# BI3.net
KiCad netlist of a schematic drawn in Altium Designer
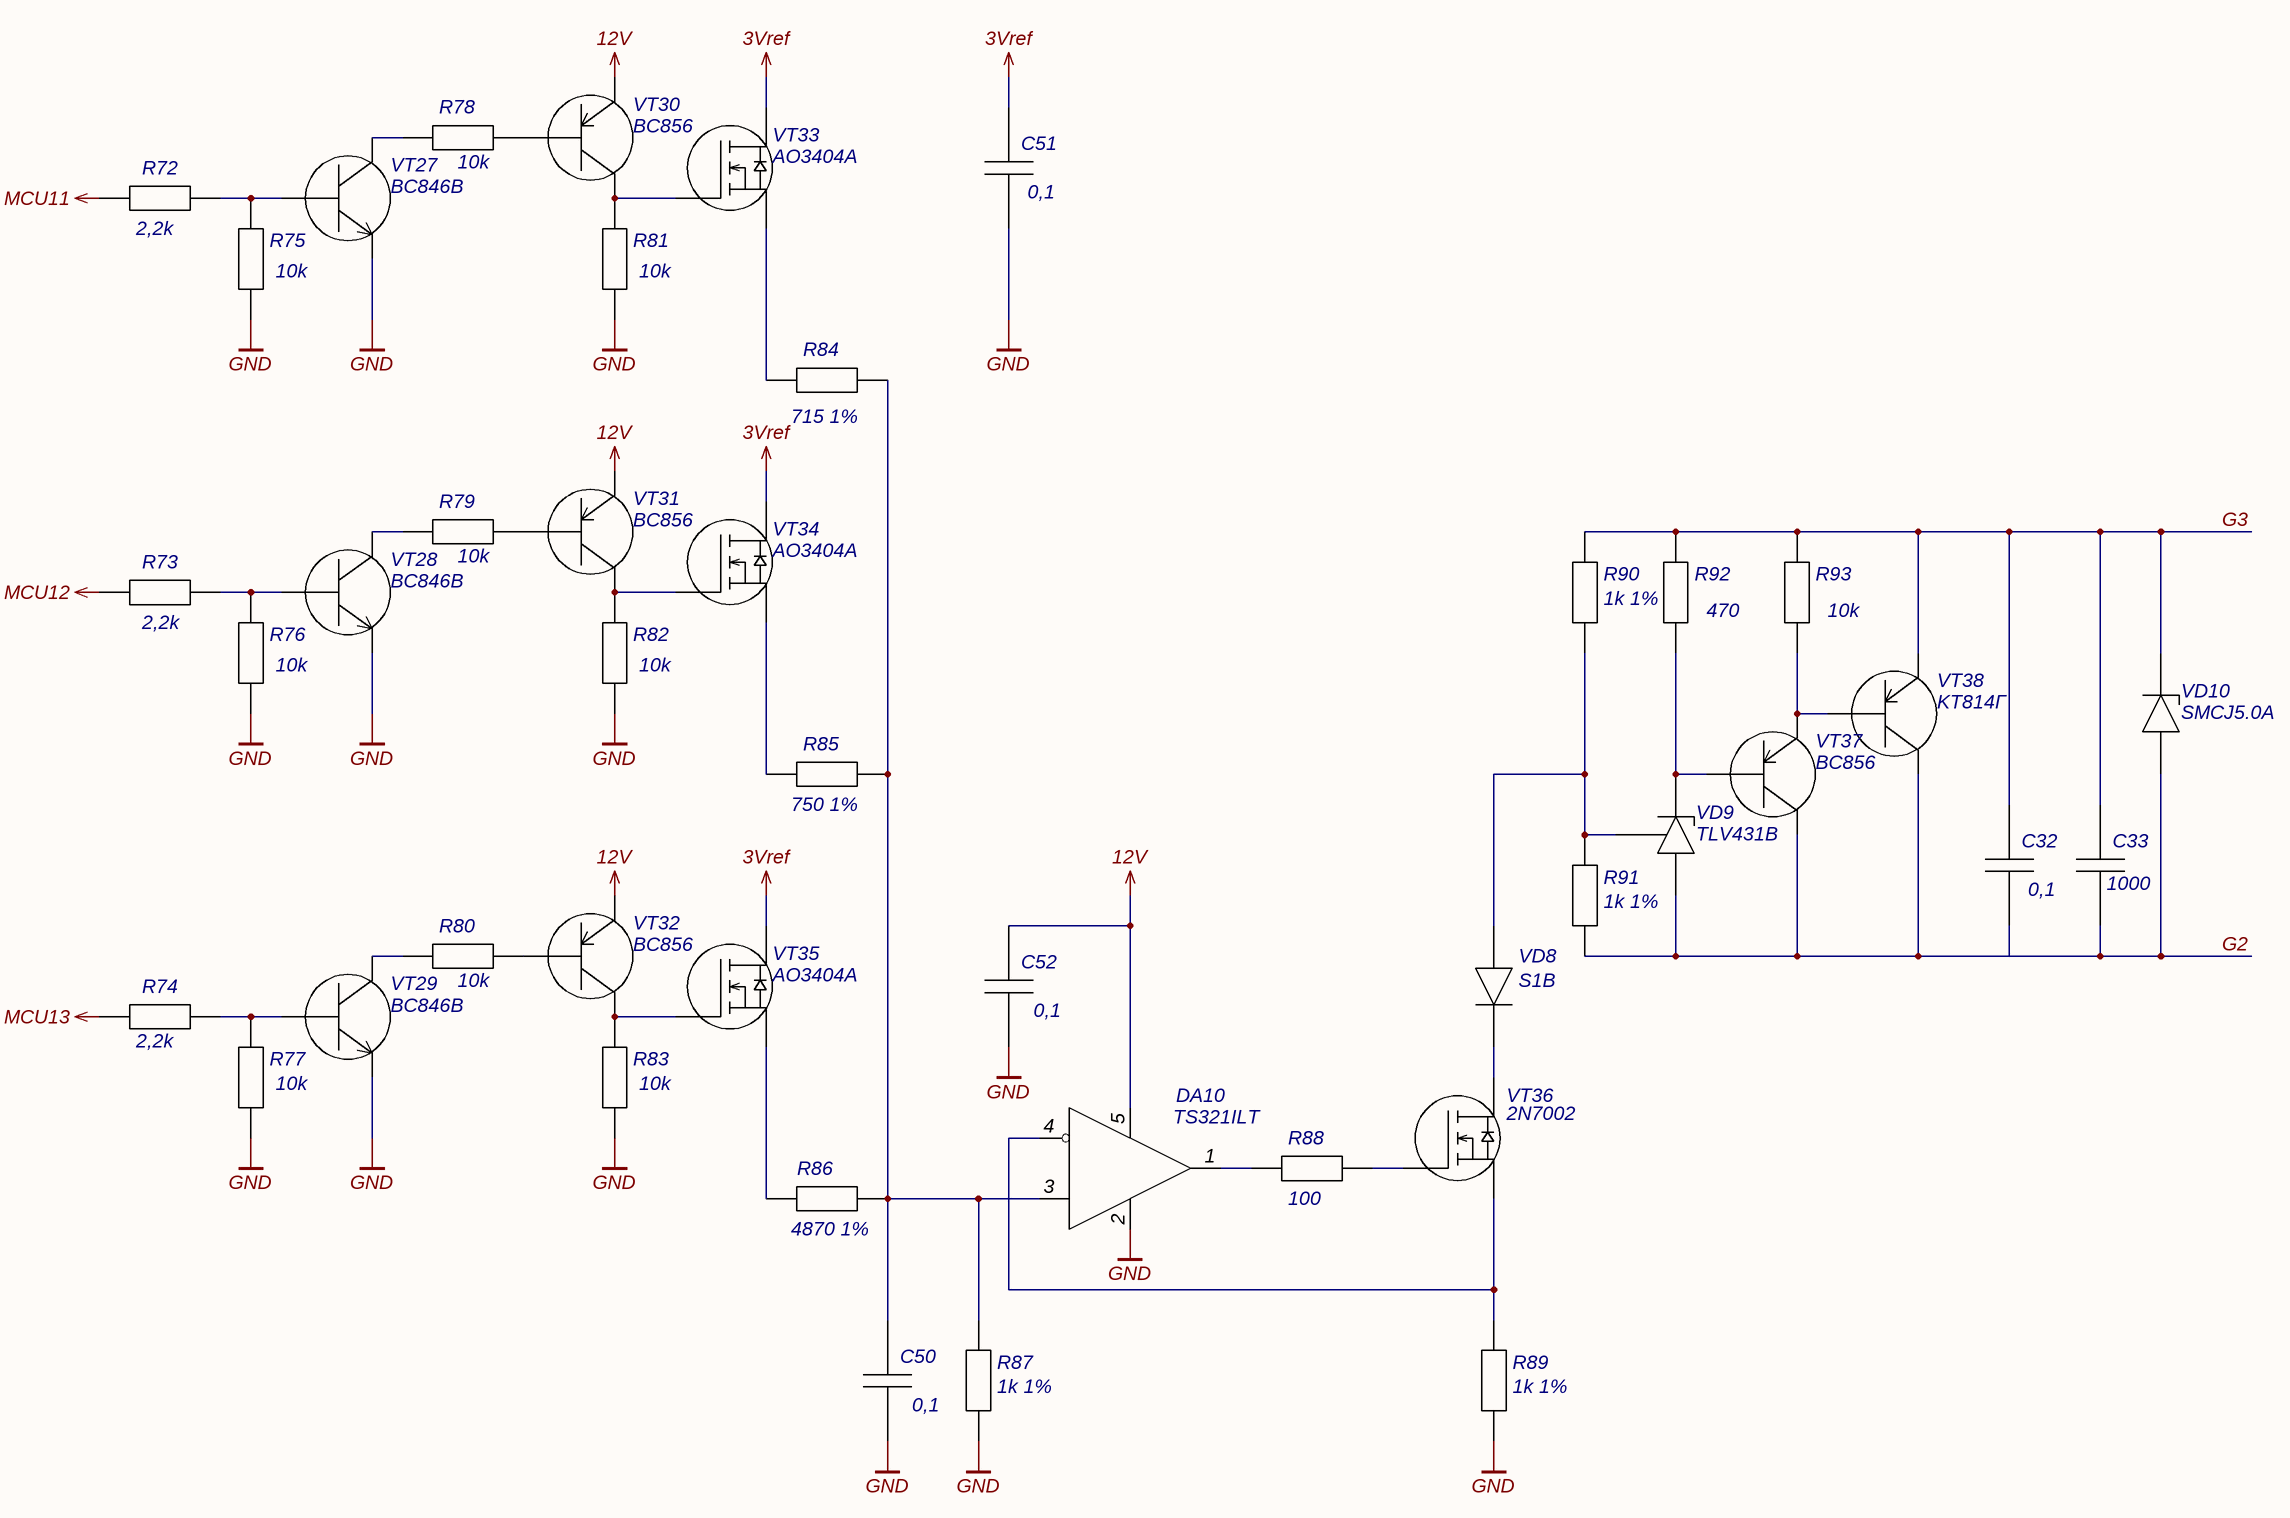
[diagram p0: BI3.SchDoc]

(export (version "E")
  (design (tool "Eeschema 10.0.6"))
  (components
    (comp (ref "C32")
      (value "0,1")
      (footprint "C0603")
      (description "Чип-конденсатор")
      (libsource (lib "Passive") (part "Chip Capasitor"))
    )
    (comp (ref "C33")
      (value "1000")
      (footprint "C0603")
      (description "Чип-конденсатор")
      (libsource (lib "Passive") (part "Chip Capasitor"))
    )
    (comp (ref "C50")
      (value "0,1")
      (footprint "C0603")
      (description "Чип-конденсатор")
      (libsource (lib "Passive") (part "Chip Capasitor"))
    )
    (comp (ref "C51")
      (value "0,1")
      (footprint "C0603")
      (description "Чип-конденсатор")
      (libsource (lib "Passive") (part "Chip Capasitor"))
    )
    (comp (ref "C52")
      (value "0,1")
      (footprint "C0603")
      (description "Чип-конденсатор")
      (libsource (lib "Passive") (part "Chip Capasitor"))
    )
    (comp (ref "DA10")
      (value "TS321ILT")
      (footprint "SOT-23-5")
      (description "1х Операционный усилитель")
      (libsource (lib "Schlib") (part "TS321ILT"))
    )
    (comp (ref "R72")
      (value "2,2k")
      (footprint "R0603")
      (description "Чип-резистор")
      (libsource (lib "") (part "Chip Resistor_1"))
    )
    (comp (ref "R73")
      (value "2,2k")
      (footprint "R0603")
      (description "Чип-резистор")
      (libsource (lib "") (part "Chip Resistor_1"))
    )
    (comp (ref "R74")
      (value "2,2k")
      (footprint "R0603")
      (description "Чип-резистор")
      (libsource (lib "") (part "Chip Resistor_1"))
    )
    (comp (ref "R75")
      (value "10k")
      (footprint "R0603")
      (description "Чип-резистор")
      (libsource (lib "Passive") (part "Chip Resistor"))
    )
    (comp (ref "R76")
      (value "10k")
      (footprint "R0603")
      (description "Чип-резистор")
      (libsource (lib "Passive") (part "Chip Resistor"))
    )
    (comp (ref "R77")
      (value "10k")
      (footprint "R0603")
      (description "Чип-резистор")
      (libsource (lib "Passive") (part "Chip Resistor"))
    )
    (comp (ref "R78")
      (value "10k")
      (footprint "R0603")
      (description "Чип-резистор")
      (libsource (lib "") (part "Chip Resistor_1"))
    )
    (comp (ref "R79")
      (value "10k")
      (footprint "R0603")
      (description "Чип-резистор")
      (libsource (lib "") (part "Chip Resistor_1"))
    )
    (comp (ref "R80")
      (value "10k")
      (footprint "R0603")
      (description "Чип-резистор")
      (libsource (lib "") (part "Chip Resistor_1"))
    )
    (comp (ref "R81")
      (value "10k")
      (footprint "R0603")
      (description "Чип-резистор")
      (libsource (lib "Passive") (part "Chip Resistor"))
    )
    (comp (ref "R82")
      (value "10k")
      (footprint "R0603")
      (description "Чип-резистор")
      (libsource (lib "Passive") (part "Chip Resistor"))
    )
    (comp (ref "R83")
      (value "10k")
      (footprint "R0603")
      (description "Чип-резистор")
      (libsource (lib "Passive") (part "Chip Resistor"))
    )
    (comp (ref "R84")
      (value "715 1%")
      (footprint "R0603")
      (description "Чип-резистор")
      (fields (field (name "PARTNUMBER") "RC0603FR-07715RL"))
      (libsource (lib "") (part "Chip Resistor_1"))
    )
    (comp (ref "R85")
      (value "750 1%")
      (footprint "R0603")
      (description "Чип-резистор")
      (fields (field (name "PARTNUMBER") "RC0603FR-07750RL"))
      (libsource (lib "") (part "Chip Resistor_1"))
    )
    (comp (ref "R86")
      (value "4870 1%")
      (footprint "R0603")
      (description "Чип-резистор")
      (fields (field (name "PARTNUMBER") "RC0603FR-074K87L"))
      (libsource (lib "") (part "Chip Resistor_1"))
    )
    (comp (ref "R87")
      (value "1k 1%")
      (footprint "R0603")
      (description "Чип-резистор")
      (fields (field (name "PARTNUMBER") "CRCW06031K00FKEAC"))
      (libsource (lib "Passive") (part "Chip Resistor"))
    )
    (comp (ref "R88")
      (value "100")
      (footprint "R0603")
      (description "Чип-резистор")
      (libsource (lib "") (part "Chip Resistor_1"))
    )
    (comp (ref "R89")
      (value "1k 1%")
      (footprint "R0603")
      (description "Чип-резистор")
      (fields (field (name "PARTNUMBER") "CRCW06031K00FKEAC"))
      (libsource (lib "Passive") (part "Chip Resistor"))
    )
    (comp (ref "R90")
      (value "1k 1%")
      (footprint "R0603")
      (description "Чип-резистор")
      (fields (field (name "PARTNUMBER") "CRCW06031K00FKEAC"))
      (libsource (lib "Passive") (part "Chip Resistor"))
    )
    (comp (ref "R91")
      (value "1k 1%")
      (footprint "R0603")
      (description "Чип-резистор")
      (fields (field (name "PARTNUMBER") "CRCW06031K00FKEAC"))
      (libsource (lib "Passive") (part "Chip Resistor"))
    )
    (comp (ref "R92")
      (value "470")
      (footprint "R0603")
      (description "Чип-резистор")
      (libsource (lib "Passive") (part "Chip Resistor"))
    )
    (comp (ref "R93")
      (value "10k")
      (footprint "R0603")
      (description "Чип-резистор")
      (libsource (lib "Passive") (part "Chip Resistor"))
    )
    (comp (ref "VD8")
      (value "S1B")
      (footprint "DO-214AC")
      (description "Диод выпрямительный, 100В")
      (fields (field (name "MANUFACTURER") "Diotec Semiconductor"))
      (libsource (lib "Schlib") (part "S1B"))
    )
    (comp (ref "VD9")
      (value "TLV431B")
      (footprint "SOT-23")
      (description "Стабилитрон регулируемый, 6В")
      (fields (field (name "MANUFACTURER") "Texas Instruments"))
      (libsource (lib "Schlib") (part "TLV431B"))
    )
    (comp (ref "VD10")
      (value "SMCJ5.0A")
      (footprint "DO-214AB")
      (description "Защитный диод, 5В")
      (fields (field (name "MANUFACTURER") "UTD Semiconductor Co.,Ltd"))
      (libsource (lib "Schlib") (part "SMCJ5.0A"))
    )
    (comp (ref "VT27")
      (value "BC846B")
      (footprint "SOT-23")
      (description "Транзистор биполярный NPN, 65В")
      (fields (field (name "MANUFACTURER") "Nexperia B.V."))
      (libsource (lib "Schlib") (part "BC846B"))
    )
    (comp (ref "VT28")
      (value "BC846B")
      (footprint "SOT-23")
      (description "Транзистор биполярный NPN, 65В")
      (fields (field (name "MANUFACTURER") "Nexperia B.V."))
      (libsource (lib "Schlib") (part "BC846B"))
    )
    (comp (ref "VT29")
      (value "BC846B")
      (footprint "SOT-23")
      (description "Транзистор биполярный NPN, 65В")
      (fields (field (name "MANUFACTURER") "Nexperia B.V."))
      (libsource (lib "Schlib") (part "BC846B"))
    )
    (comp (ref "VT30")
      (value "BC856")
      (footprint "SOT-23")
      (description "Транзистор биполярный PNP, 65В")
      (fields (field (name "MANUFACTURER") "Nexperia"))
      (libsource (lib "Schlib") (part "BC856"))
    )
    (comp (ref "VT31")
      (value "BC856")
      (footprint "SOT-23")
      (description "Транзистор биполярный PNP, 65В")
      (fields (field (name "MANUFACTURER") "Nexperia"))
      (libsource (lib "Schlib") (part "BC856"))
    )
    (comp (ref "VT32")
      (value "BC856")
      (footprint "SOT-23")
      (description "Транзистор биполярный PNP, 65В")
      (fields (field (name "MANUFACTURER") "Nexperia"))
      (libsource (lib "Schlib") (part "BC856"))
    )
    (comp (ref "VT33")
      (value "AO3404A")
      (footprint "SOT-23")
      (description "Транзистор MOSFET N-канал, 30В")
      (fields (field (name "MANUFACTURER") "UTD Semiconductor Co.,Ltd"))
      (libsource (lib "Schlib") (part "AO3404A"))
    )
    (comp (ref "VT34")
      (value "AO3404A")
      (footprint "SOT-23")
      (description "Транзистор MOSFET N-канал, 30В")
      (fields (field (name "MANUFACTURER") "UTD Semiconductor Co.,Ltd"))
      (libsource (lib "Schlib") (part "AO3404A"))
    )
    (comp (ref "VT35")
      (value "AO3404A")
      (footprint "SOT-23")
      (description "Транзистор MOSFET N-канал, 30В")
      (fields (field (name "MANUFACTURER") "UTD Semiconductor Co.,Ltd"))
      (libsource (lib "Schlib") (part "AO3404A"))
    )
    (comp (ref "VT36")
      (value "2N7002")
      (footprint "SOT-23")
      (description "Транзистор MOSFET N-канал, 60В")
      (fields (field (name "MANUFACTURER") "UTD Semiconductor Co."))
      (libsource (lib "Schlib") (part "2N7002"))
    )
    (comp (ref "VT37")
      (value "BC856")
      (footprint "SOT-23")
      (description "Транзистор биполярный PNP, 65В")
      (fields (field (name "MANUFACTURER") "Nexperia"))
      (libsource (lib "Schlib") (part "BC856"))
    )
    (comp (ref "VT38")
      (value "KT814Г")
      (footprint "TO-126")
      (description "Транзистор биполярный PNP, 100В")
      (fields (field (name "MANUFACTURER") "АО «ГРУППА КРЕМНИЙ ЭЛ»"))
      (libsource (lib "Schlib") (part "KT814Г"))
    )
  )
  (nets
    (net (code "1") (name "/G2") (class "Default")
      (node (ref "C32") (pin "1") (pinfunction "1_1") (pintype "passive"))
      (node (ref "C33") (pin "1") (pinfunction "1_1") (pintype "passive"))
      (node (ref "R91") (pin "1") (pinfunction "1_1") (pintype "passive"))
      (node (ref "VD10") (pin "1") (pinfunction "1_1") (pintype "passive"))
      (node (ref "VD9") (pin "1") (pinfunction "1_1") (pintype "passive"))
      (node (ref "VT37") (pin "2") (pinfunction "2_2") (pintype "passive"))
      (node (ref "VT38") (pin "2") (pinfunction "2_2") (pintype "passive"))
    )
    (net (code "2") (name "/G3") (class "Default")
      (node (ref "C32") (pin "2") (pinfunction "2_2") (pintype "passive"))
      (node (ref "C33") (pin "2") (pinfunction "2_2") (pintype "passive"))
      (node (ref "R90") (pin "2") (pinfunction "2_2") (pintype "passive"))
      (node (ref "R92") (pin "2") (pinfunction "2_2") (pintype "passive"))
      (node (ref "R93") (pin "2") (pinfunction "2_2") (pintype "passive"))
      (node (ref "VD10") (pin "2") (pinfunction "2_2") (pintype "passive"))
      (node (ref "VT38") (pin "1") (pinfunction "1_1") (pintype "passive"))
    )
    (net (code "3") (name "3Vref") (class "Default")
      (node (ref "C51") (pin "2") (pinfunction "2_2") (pintype "passive"))
      (node (ref "VT33") (pin "2") (pinfunction "D_2") (pintype "passive"))
      (node (ref "VT34") (pin "2") (pinfunction "D_2") (pintype "passive"))
      (node (ref "VT35") (pin "2") (pinfunction "D_2") (pintype "passive"))
    )
    (net (code "4") (name "12V") (class "Default")
      (node (ref "C52") (pin "2") (pinfunction "2_2") (pintype "passive"))
      (node (ref "DA10") (pin "5") (pinfunction "Vcc_5") (pintype "passive"))
      (node (ref "VT30") (pin "1") (pinfunction "1_1") (pintype "passive"))
      (node (ref "VT31") (pin "1") (pinfunction "1_1") (pintype "passive"))
      (node (ref "VT32") (pin "1") (pinfunction "1_1") (pintype "passive"))
    )
    (net (code "5") (name "GND") (class "Default")
      (node (ref "C50") (pin "1") (pinfunction "1_1") (pintype "passive"))
      (node (ref "C51") (pin "1") (pinfunction "1_1") (pintype "passive"))
      (node (ref "C52") (pin "1") (pinfunction "1_1") (pintype "passive"))
      (node (ref "DA10") (pin "2") (pinfunction "GND_2") (pintype "passive"))
      (node (ref "R75") (pin "1") (pinfunction "1_1") (pintype "passive"))
      (node (ref "R76") (pin "1") (pinfunction "1_1") (pintype "passive"))
      (node (ref "R77") (pin "1") (pinfunction "1_1") (pintype "passive"))
      (node (ref "R81") (pin "1") (pinfunction "1_1") (pintype "passive"))
      (node (ref "R82") (pin "1") (pinfunction "1_1") (pintype "passive"))
      (node (ref "R83") (pin "1") (pinfunction "1_1") (pintype "passive"))
      (node (ref "R87") (pin "1") (pinfunction "1_1") (pintype "passive"))
      (node (ref "R89") (pin "1") (pinfunction "1_1") (pintype "passive"))
      (node (ref "VT27") (pin "2") (pinfunction "E_2") (pintype "passive"))
      (node (ref "VT28") (pin "2") (pinfunction "E_2") (pintype "passive"))
      (node (ref "VT29") (pin "2") (pinfunction "E_2") (pintype "passive"))
    )
    (net (code "6") (name "MCU11") (class "Default")
      (node (ref "R72") (pin "1") (pinfunction "1_1") (pintype "passive"))
    )
    (net (code "7") (name "MCU12") (class "Default")
      (node (ref "R73") (pin "1") (pinfunction "1_1") (pintype "passive"))
    )
    (net (code "8") (name "MCU13") (class "Default")
      (node (ref "R74") (pin "1") (pinfunction "1_1") (pintype "passive"))
    )
    (net (code "9") (name "Net-(DA10-+)") (class "Default")
      (node (ref "C50") (pin "2") (pinfunction "2_2") (pintype "passive"))
      (node (ref "DA10") (pin "3") (pinfunction "+_3") (pintype "passive"))
      (node (ref "R84") (pin "2") (pinfunction "2_2") (pintype "passive"))
      (node (ref "R85") (pin "2") (pinfunction "2_2") (pintype "passive"))
      (node (ref "R86") (pin "2") (pinfunction "2_2") (pintype "passive"))
      (node (ref "R87") (pin "2") (pinfunction "2_2") (pintype "passive"))
    )
    (net (code "10") (name "Net-(DA10--)") (class "Default")
      (node (ref "DA10") (pin "4") (pinfunction "-_4") (pintype "passive"))
      (node (ref "R89") (pin "2") (pinfunction "2_2") (pintype "passive"))
      (node (ref "VT36") (pin "3") (pinfunction "S_3") (pintype "passive"))
    )
    (net (code "11") (name "Net-(DA10-OUT)") (class "Default")
      (node (ref "DA10") (pin "1") (pinfunction "OUT_1") (pintype "passive"))
      (node (ref "R88") (pin "1") (pinfunction "1_1") (pintype "passive"))
    )
    (net (code "12") (name "Net-(R78-Pad2)") (class "Default")
      (node (ref "R78") (pin "2") (pinfunction "2_2") (pintype "passive"))
      (node (ref "VT30") (pin "3") (pinfunction "3_3") (pintype "passive"))
    )
    (net (code "13") (name "Net-(R79-Pad2)") (class "Default")
      (node (ref "R79") (pin "2") (pinfunction "2_2") (pintype "passive"))
      (node (ref "VT31") (pin "3") (pinfunction "3_3") (pintype "passive"))
    )
    (net (code "14") (name "Net-(R80-Pad2)") (class "Default")
      (node (ref "R80") (pin "2") (pinfunction "2_2") (pintype "passive"))
      (node (ref "VT32") (pin "3") (pinfunction "3_3") (pintype "passive"))
    )
    (net (code "15") (name "Net-(R90-Pad1)") (class "Default")
      (node (ref "R90") (pin "1") (pinfunction "1_1") (pintype "passive"))
      (node (ref "R91") (pin "2") (pinfunction "2_2") (pintype "passive"))
      (node (ref "VD8") (pin "1") (pinfunction "1_1") (pintype "passive"))
      (node (ref "VD9") (pin "3") (pinfunction "3_3") (pintype "passive"))
    )
    (net (code "16") (name "Net-(R92-Pad1)") (class "Default")
      (node (ref "R92") (pin "1") (pinfunction "1_1") (pintype "passive"))
      (node (ref "VD9") (pin "2") (pinfunction "2_2") (pintype "passive"))
      (node (ref "VT37") (pin "3") (pinfunction "3_3") (pintype "passive"))
    )
    (net (code "17") (name "Net-(R93-Pad1)") (class "Default")
      (node (ref "R93") (pin "1") (pinfunction "1_1") (pintype "passive"))
      (node (ref "VT37") (pin "1") (pinfunction "1_1") (pintype "passive"))
      (node (ref "VT38") (pin "3") (pinfunction "3_3") (pintype "passive"))
    )
    (net (code "18") (name "Net-(VT27-B)") (class "Default")
      (node (ref "R72") (pin "2") (pinfunction "2_2") (pintype "passive"))
      (node (ref "R75") (pin "2") (pinfunction "2_2") (pintype "passive"))
      (node (ref "VT27") (pin "1") (pinfunction "B_1") (pintype "passive"))
    )
    (net (code "19") (name "Net-(VT27-C)") (class "Default")
      (node (ref "R78") (pin "1") (pinfunction "1_1") (pintype "passive"))
      (node (ref "VT27") (pin "3") (pinfunction "C_3") (pintype "passive"))
    )
    (net (code "20") (name "Net-(VT28-B)") (class "Default")
      (node (ref "R73") (pin "2") (pinfunction "2_2") (pintype "passive"))
      (node (ref "R76") (pin "2") (pinfunction "2_2") (pintype "passive"))
      (node (ref "VT28") (pin "1") (pinfunction "B_1") (pintype "passive"))
    )
    (net (code "21") (name "Net-(VT28-C)") (class "Default")
      (node (ref "R79") (pin "1") (pinfunction "1_1") (pintype "passive"))
      (node (ref "VT28") (pin "3") (pinfunction "C_3") (pintype "passive"))
    )
    (net (code "22") (name "Net-(VT29-B)") (class "Default")
      (node (ref "R74") (pin "2") (pinfunction "2_2") (pintype "passive"))
      (node (ref "R77") (pin "2") (pinfunction "2_2") (pintype "passive"))
      (node (ref "VT29") (pin "1") (pinfunction "B_1") (pintype "passive"))
    )
    (net (code "23") (name "Net-(VT29-C)") (class "Default")
      (node (ref "R80") (pin "1") (pinfunction "1_1") (pintype "passive"))
      (node (ref "VT29") (pin "3") (pinfunction "C_3") (pintype "passive"))
    )
    (net (code "24") (name "Net-(VT33-G)") (class "Default")
      (node (ref "R81") (pin "2") (pinfunction "2_2") (pintype "passive"))
      (node (ref "VT30") (pin "2") (pinfunction "2_2") (pintype "passive"))
      (node (ref "VT33") (pin "1") (pinfunction "G_1") (pintype "passive"))
    )
    (net (code "25") (name "Net-(VT33-S)") (class "Default")
      (node (ref "R84") (pin "1") (pinfunction "1_1") (pintype "passive"))
      (node (ref "VT33") (pin "3") (pinfunction "S_3") (pintype "passive"))
    )
    (net (code "26") (name "Net-(VT34-G)") (class "Default")
      (node (ref "R82") (pin "2") (pinfunction "2_2") (pintype "passive"))
      (node (ref "VT31") (pin "2") (pinfunction "2_2") (pintype "passive"))
      (node (ref "VT34") (pin "1") (pinfunction "G_1") (pintype "passive"))
    )
    (net (code "27") (name "Net-(VT34-S)") (class "Default")
      (node (ref "R85") (pin "1") (pinfunction "1_1") (pintype "passive"))
      (node (ref "VT34") (pin "3") (pinfunction "S_3") (pintype "passive"))
    )
    (net (code "28") (name "Net-(VT35-G)") (class "Default")
      (node (ref "R83") (pin "2") (pinfunction "2_2") (pintype "passive"))
      (node (ref "VT32") (pin "2") (pinfunction "2_2") (pintype "passive"))
      (node (ref "VT35") (pin "1") (pinfunction "G_1") (pintype "passive"))
    )
    (net (code "29") (name "Net-(VT35-S)") (class "Default")
      (node (ref "R86") (pin "1") (pinfunction "1_1") (pintype "passive"))
      (node (ref "VT35") (pin "3") (pinfunction "S_3") (pintype "passive"))
    )
    (net (code "30") (name "Net-(VT36-D)") (class "Default")
      (node (ref "VD8") (pin "2") (pinfunction "2_2") (pintype "passive"))
      (node (ref "VT36") (pin "2") (pinfunction "D_2") (pintype "passive"))
    )
    (net (code "31") (name "Net-(VT36-G)") (class "Default")
      (node (ref "R88") (pin "2") (pinfunction "2_2") (pintype "passive"))
      (node (ref "VT36") (pin "1") (pinfunction "G_1") (pintype "passive"))
    )
  )
)
